# PDB_Schematic_v1_8.net
KiCad netlist of a schematic drawn in Altium Designer
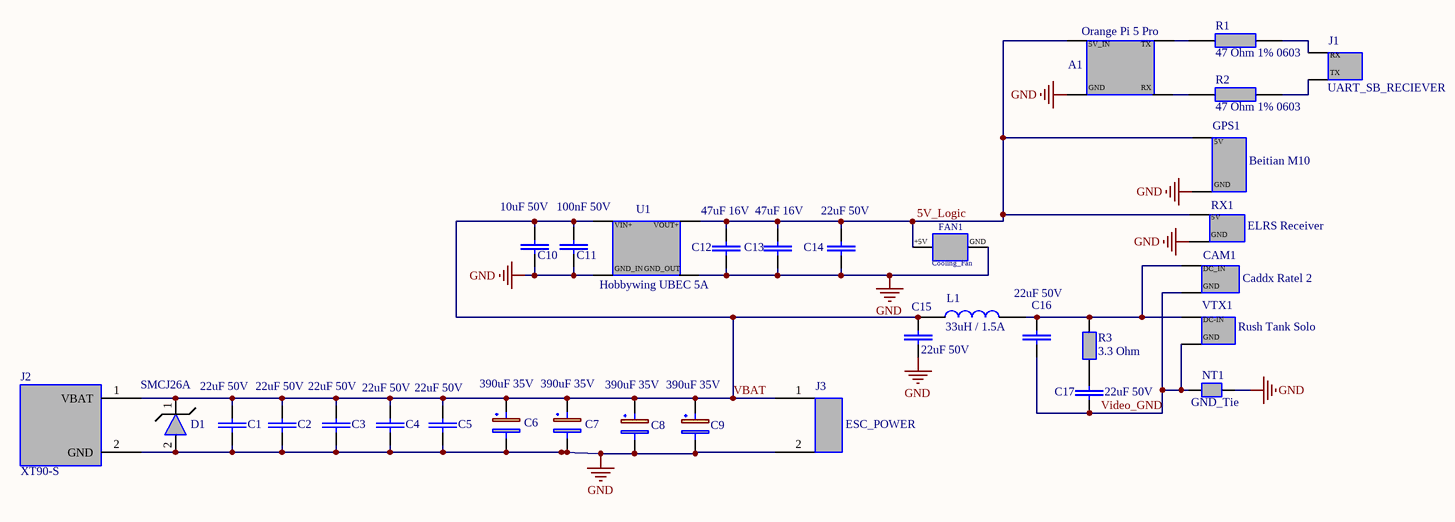
[diagram p0: PDB_Schematic_v1.8.SchDoc]

(export (version "E")
  (design (tool "Eeschema 10.0.6"))
  (components
    (comp (ref "A1")
      (value "Orange Pi 5 Pro")
      (footprint "FOOTPRINT_ORANGE_PI")
      (libsource (lib "PDB_Components_v1.0") (part "Orange Pi 5 Pro"))
    )
    (comp (ref "C1")
      (value "22uF 50V")
      (footprint "PDB_Footprints_v1.0:1210")
      (libsource (lib "PDB_Components_v1.0") (part "Cap_MLCC"))
    )
    (comp (ref "C2")
      (value "22uF 50V")
      (footprint "PDB_Footprints_v1.0:1210")
      (libsource (lib "PDB_Components_v1.0") (part "Cap_MLCC"))
    )
    (comp (ref "C3")
      (value "22uF 50V")
      (footprint "PDB_Footprints_v1.0:1210")
      (libsource (lib "PDB_Components_v1.0") (part "Cap_MLCC"))
    )
    (comp (ref "C4")
      (value "22uF 50V")
      (footprint "PDB_Footprints_v1.0:1210")
      (libsource (lib "PDB_Components_v1.0") (part "Cap_Cer_22uF_50V"))
    )
    (comp (ref "C5")
      (value "22uF 50V")
      (footprint "PDB_Footprints_v1.0:1210")
      (libsource (lib "PDB_Components_v1.0") (part "Cap_MLCC"))
    )
    (comp (ref "C6")
      (value "390uF 35V")
      (footprint "PDB_Footprints_v1.0:CAP_ELEC_D10.0_P5.0")
      (description "Low ESR Aluminum Electrolytic Capacitor, Panasonic FR Series, 390uF 35V, Radial, 5mm Lead Pitc")
      (fields (field (name "VOLTAGE") "35V") (field (name "MANUFACTURER") "Panasonic"))
      (libsource (lib "PDB_Components_v1.0") (part "Cap_Low_ESR"))
    )
    (comp (ref "C7")
      (value "390uF 35V")
      (footprint "PDB_Footprints_v1.0:CAP_ELEC_D10.0_P5.0")
      (description "Low ESR Aluminum Electrolytic Capacitor, Panasonic FR Series, 390uF 35V, Radial, 5mm Lead Pitc")
      (fields (field (name "VOLTAGE") "35V") (field (name "MANUFACTURER") "Panasonic"))
      (libsource (lib "PDB_Components_v1.0") (part "Cap_Low_ESR"))
    )
    (comp (ref "C8")
      (value "390uF 35V")
      (footprint "PDB_Footprints_v1.0:CAP_ELEC_D10.0_P5.0")
      (description "Low ESR Aluminum Electrolytic Capacitor, Panasonic FR Series, 390uF 35V, Radial, 5mm Lead Pitc")
      (fields (field (name "VOLTAGE") "35V") (field (name "MANUFACTURER") "Panasonic"))
      (libsource (lib "PDB_Components_v1.0") (part "Cap_Low_ESR"))
    )
    (comp (ref "C9")
      (value "390uF 35V")
      (footprint "PDB_Footprints_v1.0:CAP_ELEC_D10.0_P5.0")
      (description "Low ESR Aluminum Electrolytic Capacitor, Panasonic FR Series, 390uF 35V, Radial, 5mm Lead Pitc")
      (fields (field (name "VOLTAGE") "35V") (field (name "MANUFACTURER") "Panasonic"))
      (libsource (lib "PDB_Components_v1.0") (part "Cap_Low_ESR"))
    )
    (comp (ref "C10")
      (value "10uF 50V")
      (footprint "PDB_Footprints_v1.0:1206")
      (description "Ceramic Capacitor, 10 uF, 50 V, X7R Dielectric, 1206 SMD, UBEC VIN Buffer")
      (libsource (lib "PDB_Components_v1.0") (part "Cap_Cer_10uF_50V_1206"))
    )
    (comp (ref "C11")
      (value "100nF 50V")
      (footprint "PDB_Footprints_v1.0:0603")
      (description "High-Frequency Ceramic Capacitor, 100 nF, 50 V, X7R Dielectric, 0603 SMD, UBEC VIN Decoupling")
      (libsource (lib "PDB_Components_v1.0") (part "Cap_Cer_100nF_50V_0603"))
    )
    (comp (ref "C12")
      (value "47uF 16V")
      (footprint "PDB_Footprints_v1.0:1210")
      (description "Capacitor MLCC 47uF 16V X7R 1210\r\nGRM32ER71C476KE15L")
      (libsource (lib "PDB_Components_v1.0") (part "Cap_Cer_47uF_16V"))
    )
    (comp (ref "C13")
      (value "47uF 16V")
      (footprint "PDB_Footprints_v1.0:1210")
      (description "Capacitor MLCC 47uF 16V X7R 1210\r\nGRM32ER71C476KE15L")
      (libsource (lib "PDB_Components_v1.0") (part "Cap_Cer_47uF_16V"))
    )
    (comp (ref "C14")
      (value "22uF 50V")
      (footprint "PDB_Footprints_v1.0:1210")
      (description "Multilayer Ceramic Capacitor (MLCC), 22uF 50V, X7R, 1210 (3225 Metric), High-Frequency ESC Filter")
      (libsource (lib "PDB_Components_v1.0") (part "Cap_MLCC"))
    )
    (comp (ref "C15")
      (value "22uF 50V")
      (footprint "PDB_Footprints_v1.0:1210")
      (libsource (lib "PDB_Components_v1.0") (part "Cap_Cer_22uF_50V"))
    )
    (comp (ref "C16")
      (value "22uF 50V")
      (footprint "PDB_Footprints_v1.0:1210")
      (libsource (lib "PDB_Components_v1.0") (part "Cap_Cer_22uF_50V"))
    )
    (comp (ref "C17")
      (value "22uF 50V")
      (footprint "PDB_Footprints_v1.0:1206")
      (description "Capacitor MLCC 22uF 50V ±20% X7R 1206 (3216 Metric)")
      (libsource (lib "PDB_Components_v1.0") (part "Cap_Cer_22uF_50V_1206"))
    )
    (comp (ref "CAM1")
      (value "Caddx Ratel 2")
      (footprint "PDB_Footprints_v1.0:FOOTPRINT_Caddx_Ratel_2")
      (description "Analog FPV Micro Camera, 1200TVL, Ultra Low Light Starlight")
      (libsource (lib "PDB_Components_v1.0") (part "Caddx Ratel 2"))
    )
    (comp (ref "D1")
      (value "SMCJ26A")
      (footprint "PDB_Footprints_v1.0:DIODE_SMC")
      (description "Transient Voltage Suppressor (TVS) Diode, Unidirectional, 26V Vrwm, 1500W Peak, DO-214AB (SMC)")
      (libsource (lib "PDB_Components_v1.0") (part "SMCJ26A"))
    )
    (comp (ref "FAN1")
      (value "Cooling_Fan")
      (footprint "PDB_Footprints_v1.0:FOOTPRINT_FAN_5V")
      (description "V DC Micro Cooling Fan, 25x25x10mm Active Cooling")
      (libsource (lib "PDB_Components_v1.0") (part "Cooling Fan 5V"))
    )
    (comp (ref "GPS1")
      (value "Beitian M10")
      (footprint "PDB_Footprints_v1.0:FOOTPRINT_BEITIAN_M10")
      (description "GNSS GPS + Compass Module, M10 Platform, UART & I2C Interface")
      (libsource (lib "PDB_Components_v1.0") (part "Beitian M10"))
    )
    (comp (ref "J1")
      (value "UART_SB_RECIEVER")
      (footprint "PDB_Footprints_v1.0:UART_SPEEDYBEE_RECIEVER")
      (libsource (lib "PDB_Components_v1.0") (part "UART_SPEEDYBEE_RECIEVER"))
    )
    (comp (ref "J2")
      (value "XT90-S")
      (footprint "PDB_Footprints_v1.0:XT90-S_PWR")
      (description "High-Current DC Power Connector with Integrated Anti-Spark Resistance, Amass XT90-S, 90A Peak")
      (libsource (lib "PDB_Components_v1.0") (part "XT90-S"))
    )
    (comp (ref "J3")
      (value "ESC_POWER")
      (footprint "PDB_Footprints_v1.0:PADS_ESC_PWR")
      (description "Wire-to-Board Solder Pads Array, 1x2, 2.54mm Pitch")
      (libsource (lib "PDB_Components_v1.0") (part "PADS_WIRE_1X2"))
    )
    (comp (ref "L1")
      (value "33uH / 1.5A")
      (footprint "PDB_Footprints_v1.0:FOOTPRINT_INDUCTOR_SRN6045")
      (description "Semi-Shielded Power Inductor, Bourns SRN6045 Series, 33uH 2.5A, 0.15 Ohm DCR, LC Video Filter")
      (fields (field (name "MANUFACTURER") "Bourns") (field (name "MANUFACTURER PART NUMBER") "SRN6045-330M"))
      (libsource (lib "PDB_Components_v1.0") (part "Inductor_SMD"))
    )
    (comp (ref "NT1")
      (value "GND_Tie")
      (footprint "PDB_Footprints_v1.0:NET_TIE_0.2MM")
      (description "Net-Tie zero-ohm bridge for ground separation")
      (libsource (lib "PDB_Components_v1.0") (part "NET_TIE"))
    )
    (comp (ref "R1")
      (value "47 Ohm 1% 0603")
      (footprint "PDB_Footprints_v1.0:0603")
      (fields (field (name "PART NUMBER") "RC0603FR-0747RL") (field (name "MANUFACTURER") "Yageo"))
      (libsource (lib "PDB_Components_v1.0") (part "Res_SMD"))
    )
    (comp (ref "R2")
      (value "47 Ohm 1% 0603")
      (footprint "PDB_Footprints_v1.0:0603")
      (fields (field (name "PART NUMBER") "RC0603FR-0747RL") (field (name "MANUFACTURER") "Yageo"))
      (libsource (lib "PDB_Components_v1.0") (part "Res_SMD"))
    )
    (comp (ref "R3")
      (value "3.3 Ohm")
      (footprint "PDB_Footprints_v1.0:0603")
      (description "Resistor SMD 3.3 Ohm 1% 1/10W (0.1W) 0603 Thick Film")
      (libsource (lib "PDB_Components_v1.0") (part "Res_3.3Ohm_0603"))
    )
    (comp (ref "RX1")
      (value "ELRS Receiver")
      (footprint "PDB_Footprints_v1.0:FOOTPRINT_ELRS_RX")
      (description "ExpressLRS 2.4GHz True Diversity Radio Receiver Module")
      (libsource (lib "PDB_Components_v1.0") (part "ExpressLRS RX"))
    )
    (comp (ref "U1")
      (value "Hobbywing UBEC 5A")
      (footprint "PDB_Footprints_v1.0:UBEC_Hobbywing_5A")
      (fields (field (name "MANUFACTURER") "Hobbywing") (field (name "PART NUMBER") "HW30607000"))
      (libsource (lib "PDB_Components_v1.0") (part "UBEC_Hobbywing_5A"))
    )
    (comp (ref "VTX1")
      (value "Rush Tank Solo")
      (footprint "PDB_Footprints_v1.0:FOOTPRINT_VTX_RUSH_SOLO")
      (description "5.8GHz VTX 1.6W Video Transmitter Module")
      (libsource (lib "PDB_Components_v1.0") (part "Rush Tank Solo 1.6W"))
    )
  )
  (nets
    (net (code "1") (name "/5V_Logic") (class "Default")
      (node (ref "A1") (pin "1") (pinfunction "5V_IN_1") (pintype "power_in"))
      (node (ref "C12") (pin "2") (pinfunction "-_2") (pintype "passive"))
      (node (ref "C13") (pin "2") (pinfunction "-_2") (pintype "passive"))
      (node (ref "C14") (pin "2") (pinfunction "-_2") (pintype "passive"))
      (node (ref "FAN1") (pin "1") (pinfunction "+5V_1") (pintype "power_in"))
      (node (ref "GPS1") (pin "1") (pinfunction "5V_1") (pintype "power_in"))
      (node (ref "RX1") (pin "1") (pinfunction "5V_1") (pintype "power_in"))
      (node (ref "U1") (pin "2") (pinfunction "+5.1V_2") (pintype "power_in"))
    )
    (net (code "3") (name "/VBAT") (class "Default")
      (node (ref "C1") (pin "2") (pinfunction "-_2") (pintype "passive"))
      (node (ref "C10") (pin "2") (pinfunction "-_2") (pintype "passive"))
      (node (ref "C11") (pin "2") (pinfunction "-_2") (pintype "passive"))
      (node (ref "C15") (pin "2") (pinfunction "-_2") (pintype "passive"))
      (node (ref "C2") (pin "2") (pinfunction "-_2") (pintype "passive"))
      (node (ref "C3") (pin "2") (pinfunction "-_2") (pintype "passive"))
      (node (ref "C4") (pin "2") (pinfunction "-_2") (pintype "passive"))
      (node (ref "C5") (pin "2") (pinfunction "-_2") (pintype "passive"))
      (node (ref "C6") (pin "1") (pinfunction "+_1") (pintype "passive"))
      (node (ref "C7") (pin "1") (pinfunction "+_1") (pintype "passive"))
      (node (ref "C8") (pin "1") (pinfunction "+_1") (pintype "passive"))
      (node (ref "C9") (pin "1") (pinfunction "+_1") (pintype "passive"))
      (node (ref "D1") (pin "1") (pinfunction "k_1") (pintype "power_in"))
      (node (ref "J2") (pin "1") (pinfunction "VBAT_1") (pintype "power_in"))
      (node (ref "J3") (pin "1") (pintype "passive"))
      (node (ref "L1") (pin "1") (pinfunction "1_1") (pintype "passive"))
      (node (ref "U1") (pin "1") (pinfunction "VIN+_1") (pintype "power_in"))
    )
    (net (code "4") (name "/Video_GND") (class "Default")
      (node (ref "C16") (pin "1") (pinfunction "+_1") (pintype "passive"))
      (node (ref "C17") (pin "1") (pinfunction "+_1") (pintype "passive"))
      (node (ref "CAM1") (pin "2") (pinfunction "GND_2") (pintype "power_in"))
      (node (ref "NT1") (pin "2") (pinfunction "Video_GND_2") (pintype "power_in"))
      (node (ref "VTX1") (pin "2") (pinfunction "GND_2") (pintype "power_in"))
    )
    (net (code "5") (name "GND") (class "Default")
      (node (ref "A1") (pin "2") (pinfunction "GND_2") (pintype "power_in"))
      (node (ref "C1") (pin "1") (pinfunction "+_1") (pintype "passive"))
      (node (ref "C10") (pin "1") (pinfunction "+_1") (pintype "passive"))
      (node (ref "C11") (pin "1") (pinfunction "+_1") (pintype "passive"))
      (node (ref "C12") (pin "1") (pinfunction "+_1") (pintype "passive"))
      (node (ref "C13") (pin "1") (pinfunction "+_1") (pintype "passive"))
      (node (ref "C14") (pin "1") (pinfunction "+_1") (pintype "passive"))
      (node (ref "C15") (pin "1") (pinfunction "+_1") (pintype "passive"))
      (node (ref "C2") (pin "1") (pinfunction "+_1") (pintype "passive"))
      (node (ref "C3") (pin "1") (pinfunction "+_1") (pintype "passive"))
      (node (ref "C4") (pin "1") (pinfunction "+_1") (pintype "passive"))
      (node (ref "C5") (pin "1") (pinfunction "+_1") (pintype "passive"))
      (node (ref "C6") (pin "2") (pinfunction "-_2") (pintype "passive"))
      (node (ref "C7") (pin "2") (pinfunction "-_2") (pintype "passive"))
      (node (ref "C8") (pin "2") (pinfunction "-_2") (pintype "passive"))
      (node (ref "C9") (pin "2") (pinfunction "-_2") (pintype "passive"))
      (node (ref "D1") (pin "2") (pinfunction "A_2") (pintype "power_in"))
      (node (ref "FAN1") (pin "2") (pinfunction "GND_2") (pintype "passive"))
      (node (ref "GPS1") (pin "2") (pinfunction "GND_2") (pintype "power_in"))
      (node (ref "J2") (pin "2") (pinfunction "GND_2") (pintype "power_in"))
      (node (ref "J3") (pin "2") (pintype "passive"))
      (node (ref "NT1") (pin "1") (pinfunction "GND_1") (pintype "power_in"))
      (node (ref "RX1") (pin "2") (pinfunction "GND_2") (pintype "power_in"))
      (node (ref "U1") (pin "3") (pinfunction "GND_IN_3") (pintype "power_in"))
      (node (ref "U1") (pin "4") (pinfunction "GND_OUT_4") (pintype "power_in"))
    )
    (net (code "6") (name "Net-(A1-+5.1V)") (class "Default")
      (node (ref "A1") (pin "3") (pinfunction "+5.1V_3") (pintype "passive"))
      (node (ref "R1") (pin "1") (pinfunction "1_1") (pintype "passive"))
    )
    (net (code "7") (name "Net-(A1-RX)") (class "Default")
      (node (ref "A1") (pin "4") (pinfunction "RX_4") (pintype "passive"))
      (node (ref "R2") (pin "1") (pinfunction "1_1") (pintype "passive"))
    )
    (net (code "8") (name "Net-(C16--)") (class "Default")
      (node (ref "C16") (pin "2") (pinfunction "-_2") (pintype "passive"))
      (node (ref "CAM1") (pin "1") (pinfunction "DC_IN_1") (pintype "power_in"))
      (node (ref "L1") (pin "2") (pinfunction "2_2") (pintype "passive"))
      (node (ref "R3") (pin "2") (pinfunction "2_2") (pintype "passive"))
      (node (ref "VTX1") (pin "1") (pinfunction "(7-36V)_1") (pintype "power_in"))
    )
    (net (code "9") (name "Net-(C17--)") (class "Default")
      (node (ref "C17") (pin "2") (pinfunction "-_2") (pintype "passive"))
      (node (ref "R3") (pin "1") (pinfunction "1_1") (pintype "passive"))
    )
    (net (code "10") (name "Net-(J1-RX)") (class "Default")
      (node (ref "J1") (pin "1") (pinfunction "RX_1") (pintype "power_in"))
      (node (ref "R1") (pin "2") (pinfunction "2_2") (pintype "passive"))
    )
    (net (code "11") (name "Net-(J1-TX)") (class "Default")
      (node (ref "J1") (pin "2") (pinfunction "TX_2") (pintype "power_in"))
      (node (ref "R2") (pin "2") (pinfunction "2_2") (pintype "passive"))
    )
  )
)
